# SAML21_Xplained_Pro_EDBG.net
KiCad netlist of a schematic drawn in Altium Designer
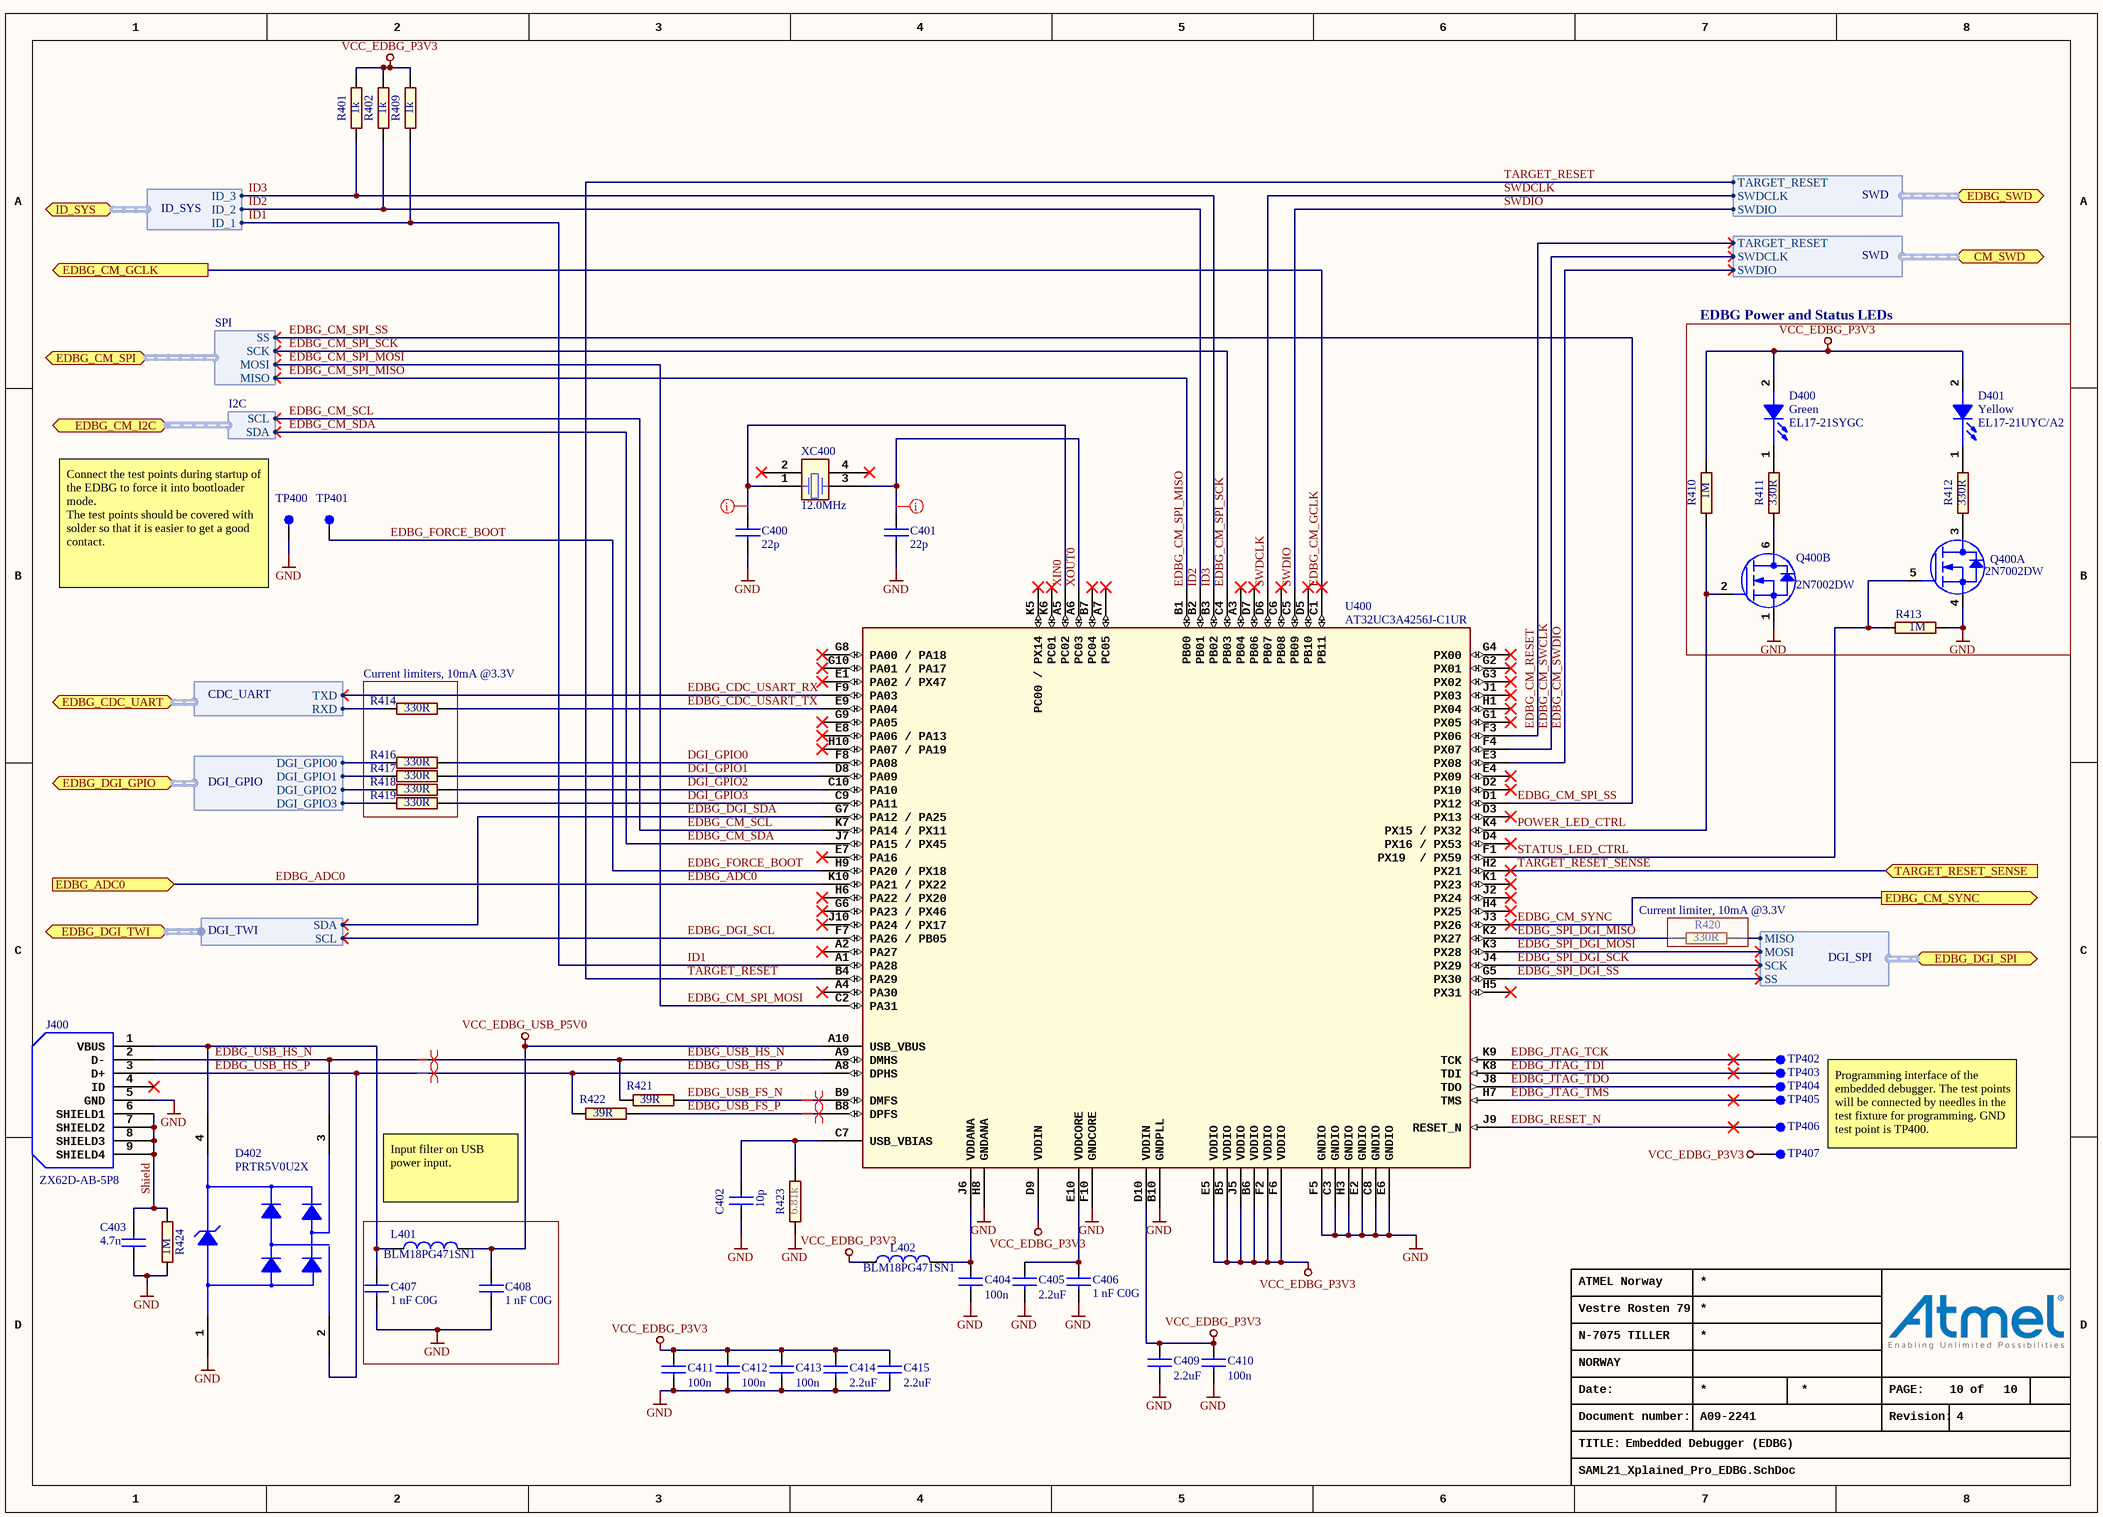
[diagram p0: SAML21_Xplained_Pro_EDBG.SchDoc]

(export (version "E")
  (design (tool "Eeschema 10.0.6"))
  (components
    (comp (ref "C400")
      (value "22p")
      (footprint "AP1-00053")
      (description "Ceramic capacitor, SMD 0402, NP0, 50V, +/-5%")
      (fields (field (name "TOLERANCE") "50V, +/-5%"))
      (libsource (lib "AltiumDbLib") (part "CAP-NONPOL"))
    )
    (comp (ref "C401")
      (value "22p")
      (footprint "AP1-00053")
      (description "Ceramic capacitor, SMD 0402, NP0, 50V, +/-5%")
      (fields (field (name "TOLERANCE") "50V, +/-5%"))
      (libsource (lib "AltiumDbLib") (part "CAP-NONPOL"))
    )
    (comp (ref "C402")
      (value "10p")
      (footprint "AP1-00053")
      (description "Ceramic capacitor, SMD 0402, NP0, 50V, +/-5%")
      (fields (field (name "TOLERANCE") "50V, +/-5%"))
      (libsource (lib "AltiumDbLib") (part "CAP-NONPOL"))
    )
    (comp (ref "C403")
      (value "4.7n")
      (footprint "AP1-00053")
      (description "Ceramic capacitor, SMD 0402, X7R, 25V, +/-10%")
      (fields (field (name "TOLERANCE") "25V, +/-10%") (field (name "Comment") "CAP-NONPOL"))
      (libsource (lib "AltiumDbLib") (part "CAP-NONPOL"))
    )
    (comp (ref "C404")
      (value "100n")
      (footprint "AP1-00053")
      (description "Ceramic capacitor, SMD 0402, X7R, 16V, +/-10%")
      (fields (field (name "TOLERANCE") "16V, +/-10%") (field (name "MANUFACTURER") "Kemet"))
      (libsource (lib "AltiumDbLib") (part "CAP-NONPOL"))
    )
    (comp (ref "C405")
      (value "2.2uF")
      (footprint "AP1-00053")
      (description "Ceramic capacitor, SMD 0402, X5R, 6.3V, +/-20%")
      (fields (field (name "TOLERANCE") "±20%") (field (name "MANUFACTURER") "Kemet"))
      (libsource (lib "AltiumDbLib") (part "CAP-NONPOL"))
    )
    (comp (ref "C406")
      (value "1 nF C0G")
      (footprint "AP1-00053")
      (description "Ceramic capacitor, SMD 0402, C0G, 50V, +/-5%")
      (fields (field (name "TOLERANCE") "5%") (field (name "MANUFACTURER") "Murata"))
      (libsource (lib "AltiumDbLib") (part "CAP-NONPOL"))
    )
    (comp (ref "C407")
      (value "1 nF C0G")
      (footprint "AP1-00053")
      (description "Ceramic capacitor, SMD 0402, C0G, 50V, +/-5%")
      (fields (field (name "TOLERANCE") "5%") (field (name "MANUFACTURER") "Murata"))
      (libsource (lib "AltiumDbLib") (part "CAP-NONPOL"))
    )
    (comp (ref "C408")
      (value "1 nF C0G")
      (footprint "AP1-00053")
      (description "Ceramic capacitor, SMD 0402, C0G, 50V, +/-5%")
      (fields (field (name "TOLERANCE") "5%") (field (name "MANUFACTURER") "Murata"))
      (libsource (lib "AltiumDbLib") (part "CAP-NONPOL"))
    )
    (comp (ref "C409")
      (value "2.2uF")
      (footprint "AP1-00053")
      (description "Ceramic capacitor, SMD 0402, X5R, 6.3V, +/-20%")
      (fields (field (name "TOLERANCE") "±20%") (field (name "MANUFACTURER") "Kemet"))
      (libsource (lib "AltiumDbLib") (part "CAP-NONPOL"))
    )
    (comp (ref "C410")
      (value "100n")
      (footprint "AP1-00053")
      (description "Ceramic capacitor, SMD 0402, X7R, 16V, +/-10%")
      (fields (field (name "TOLERANCE") "16V, +/-10%") (field (name "MANUFACTURER") "Kemet"))
      (libsource (lib "AltiumDbLib") (part "CAP-NONPOL"))
    )
    (comp (ref "C411")
      (value "100n")
      (footprint "AP1-00053")
      (description "Ceramic capacitor, SMD 0402, X7R, 16V, +/-10%")
      (fields (field (name "TOLERANCE") "16V, +/-10%") (field (name "MANUFACTURER") "Kemet"))
      (libsource (lib "AltiumDbLib") (part "CAP-NONPOL"))
    )
    (comp (ref "C412")
      (value "100n")
      (footprint "AP1-00053")
      (description "Ceramic capacitor, SMD 0402, X7R, 16V, +/-10%")
      (fields (field (name "TOLERANCE") "16V, +/-10%") (field (name "MANUFACTURER") "Kemet"))
      (libsource (lib "AltiumDbLib") (part "CAP-NONPOL"))
    )
    (comp (ref "C413")
      (value "100n")
      (footprint "AP1-00053")
      (description "Ceramic capacitor, SMD 0402, X7R, 16V, +/-10%")
      (fields (field (name "TOLERANCE") "16V, +/-10%") (field (name "MANUFACTURER") "Kemet"))
      (libsource (lib "AltiumDbLib") (part "CAP-NONPOL"))
    )
    (comp (ref "C414")
      (value "2.2uF")
      (footprint "AP1-00053")
      (description "Ceramic capacitor, SMD 0402, X5R, 6.3V, +/-20%")
      (fields (field (name "TOLERANCE") "±20%") (field (name "MANUFACTURER") "Kemet"))
      (libsource (lib "AltiumDbLib") (part "CAP-NONPOL"))
    )
    (comp (ref "C415")
      (value "2.2uF")
      (footprint "AP1-00053")
      (description "Ceramic capacitor, SMD 0402, X5R, 6.3V, +/-20%")
      (fields (field (name "TOLERANCE") "±20%") (field (name "MANUFACTURER") "Kemet"))
      (libsource (lib "AltiumDbLib") (part "CAP-NONPOL"))
    )
    (comp (ref "D400")
      (value "Green")
      (footprint "AP4-00013")
      (description "LED, Green, Wave length=575nm, SMD 0805, ±70°")
      (fields
        (field (name "ALTIUM_VALUE") "EL17-21SYGC")
        (field (name "MANUFACTURER") "Everlight")
        (field (name "MPN") "EL17-21SYGC")
      )
      (libsource (lib "AltiumDbLib") (part "LED_12"))
    )
    (comp (ref "D401")
      (value "Yellow")
      (footprint "AP4-00013")
      (description "LED, Yellow, Wave length=591nm, SMD 0805, ±70°")
      (fields
        (field (name "ALTIUM_VALUE") "EL17-21UYC/A2")
        (field (name "MANUFACTURER") "Everlight")
        (field (name "MPN") "17-21UYC/S530-A3/TR8")
      )
      (libsource (lib "AltiumDbLib") (part "LED_12"))
    )
    (comp (ref "D402")
      (value "PRTR5V0U2X")
      (footprint "AP4-00001")
      (description "Double rail-to-rail USB ESD protection diode")
      (fields (field (name "MANUFACTURER") "Philips"))
      (libsource (lib "AltiumDbLib") (part "PRTR5V0U2X"))
    )
    (comp (ref "J400")
      (value "ZX62D-AB-5P8")
      (footprint "AP8-00852")
      (description "Micro USB AB Connector, Standard SMT + DIP")
      (fields (field (name "Comment") "2,000 pieces per reel"))
      (libsource (lib "AltiumDbLib") (part "USB_AB"))
    )
    (comp (ref "L401")
      (value "BLM18PG471SN1")
      (footprint "AP3-00005")
      (description "SMD RF inductor 0603. Z=470Ohm (@100MHz), Max R(dc)=0.65Ohm, Max current=1A")
      (fields (field (name "TOLERANCE") "±25%") (field (name "MANUFACTURER") "Murata"))
      (libsource (lib "AltiumDbLib") (part "INDUCTOR"))
    )
    (comp (ref "L402")
      (value "BLM18PG471SN1")
      (footprint "AP3-00005")
      (description "SMD RF inductor 0603. Z=470Ohm (@100MHz), Max R(dc)=0.65Ohm, Max current=1A")
      (fields (field (name "TOLERANCE") "±25%") (field (name "MANUFACTURER") "Murata"))
      (libsource (lib "AltiumDbLib") (part "INDUCTOR"))
    )
    (comp (ref "Q400")
      (value "2N7002DW")
      (footprint "AP5-00001")
      (description "Dual N-Channel MOSFET, 60V, 115mA cont,RDS(ON) < 7.5 Ohm @50mA@5V, SOT-363")
      (fields
        (field (name "MANUFACTURER") "Fairchild")
        (field (name "Comment") "Same as 2N7002 but with two MOSFETs in one package")
      )
      (libsource (lib "AltiumDbLib") (part "MOSFET_DUAL_N_S2G2D1S1G1D2"))
    )
    (comp (ref "R401")
      (value "1k")
      (footprint "AP2-00000")
      (description "Thick film resistor, SMD 0402, 1/16W, 1%")
      (fields (field (name "TOLERANCE") "1 %") (field (name "Comment") "R2"))
      (libsource (lib "") (part "R2_4"))
    )
    (comp (ref "R402")
      (value "1k")
      (footprint "AP2-00000")
      (description "Thick film resistor, SMD 0402, 1/16W, 1%")
      (fields (field (name "TOLERANCE") "1 %") (field (name "Comment") "R2"))
      (libsource (lib "") (part "R2_4"))
    )
    (comp (ref "R409")
      (value "1k")
      (footprint "AP2-00000")
      (description "Thick film resistor, SMD 0402, 1/16W, 1%")
      (fields (field (name "TOLERANCE") "1 %") (field (name "Comment") "R2"))
      (libsource (lib "") (part "R2_4"))
    )
    (comp (ref "R410")
      (value "1M")
      (footprint "AP2-00011")
      (description "Thick film resistor, SMD 0402, 1/16W, 1%")
      (fields (field (name "TOLERANCE") "1 %") (field (name "MANUFACTURER") "KOA"))
      (libsource (lib "") (part "R2_4"))
    )
    (comp (ref "R411")
      (value "330R")
      (footprint "AP2-00011")
      (description "Thick film resistor, SMD 0402, 1/16W, 1%")
      (fields (field (name "TOLERANCE") "1 %") (field (name "Comment") "R2"))
      (libsource (lib "") (part "R2_4"))
    )
    (comp (ref "R412")
      (value "330R")
      (footprint "AP2-00011")
      (description "Thick film resistor, SMD 0402, 1/16W, 1%")
      (fields (field (name "TOLERANCE") "1 %") (field (name "Comment") "R2"))
      (libsource (lib "") (part "R2_4"))
    )
    (comp (ref "R413")
      (value "1M")
      (footprint "AP2-00011")
      (description "Thick film resistor, SMD 0402, 1/16W, 1%")
      (fields (field (name "TOLERANCE") "1 %") (field (name "MANUFACTURER") "KOA"))
      (libsource (lib "") (part "R2_1"))
    )
    (comp (ref "R414")
      (value "330R")
      (footprint "AP2-00000")
      (description "Thick film resistor, SMD 0402, 1/16W, 1%")
      (fields (field (name "TOLERANCE") "1 %") (field (name "Comment") "R2"))
      (libsource (lib "AltiumDbLib") (part "R2"))
    )
    (comp (ref "R416")
      (value "330R")
      (footprint "AP2-00000")
      (description "Thick film resistor, SMD 0402, 1/16W, 1%")
      (fields (field (name "TOLERANCE") "1 %") (field (name "Comment") "R2"))
      (libsource (lib "AltiumDbLib") (part "R2"))
    )
    (comp (ref "R417")
      (value "330R")
      (footprint "AP2-00000")
      (description "Thick film resistor, SMD 0402, 1/16W, 1%")
      (fields (field (name "TOLERANCE") "1 %") (field (name "Comment") "R2"))
      (libsource (lib "AltiumDbLib") (part "R2"))
    )
    (comp (ref "R418")
      (value "330R")
      (footprint "AP2-00000")
      (description "Thick film resistor, SMD 0402, 1/16W, 1%")
      (fields (field (name "TOLERANCE") "1 %") (field (name "Comment") "R2"))
      (libsource (lib "AltiumDbLib") (part "R2"))
    )
    (comp (ref "R419")
      (value "330R")
      (footprint "AP2-00000")
      (description "Thick film resistor, SMD 0402, 1/16W, 1%")
      (fields (field (name "TOLERANCE") "1 %") (field (name "Comment") "R2"))
      (libsource (lib "AltiumDbLib") (part "R2"))
    )
    (comp (ref "R420")
      (value "330R")
      (footprint "AP2-00000")
      (description "Thick film resistor, SMD 0402, 1/16W, 1%")
      (fields (field (name "TOLERANCE") "1 %") (field (name "Comment") "R2"))
      (libsource (lib "AltiumDbLib") (part "R2"))
    )
    (comp (ref "R421")
      (value "39R")
      (footprint "AP2-00011")
      (description "Thick film resistor, SMD 0402, 1/16W, 1%")
      (fields (field (name "TOLERANCE") "1 %") (field (name "Comment") "R2"))
      (libsource (lib "") (part "R2_3"))
    )
    (comp (ref "R422")
      (value "39R")
      (footprint "AP2-00011")
      (description "Thick film resistor, SMD 0402, 1/16W, 1%")
      (fields (field (name "TOLERANCE") "1 %") (field (name "Comment") "R2"))
      (libsource (lib "") (part "R2_3"))
    )
    (comp (ref "R423")
      (value "6.81k")
      (footprint "AP2-00011")
      (description "Thick film resistor, SMD 0402, 1/16W, 1%")
      (fields (field (name "TOLERANCE") "1%") (field (name "Comment") "R2"))
      (libsource (lib "") (part "R2_4"))
    )
    (comp (ref "R424")
      (value "1M")
      (footprint "AP2-00011")
      (description "Thick film resistor, SMD 0402, 1/16W, 1%")
      (fields (field (name "TOLERANCE") "1 %") (field (name "MANUFACTURER") "KOA"))
      (libsource (lib "") (part "R2_2"))
    )
    (comp (ref "TP400")
      (value "TESTPAD")
      (footprint "AP8-00010")
      (description "Single SMD testpad")
      (libsource (lib "AltiumDbLib") (part "TESTPOINT"))
    )
    (comp (ref "TP401")
      (value "TESTPAD")
      (footprint "AP8-00010")
      (description "Single SMD testpad")
      (libsource (lib "AltiumDbLib") (part "TESTPOINT"))
    )
    (comp (ref "TP402")
      (value "TESTPAD")
      (footprint "AP8-00010")
      (description "Single SMD testpad")
      (libsource (lib "AltiumDbLib") (part "TESTPOINT"))
    )
    (comp (ref "TP403")
      (value "TESTPAD")
      (footprint "AP8-00010")
      (description "Single SMD testpad")
      (libsource (lib "AltiumDbLib") (part "TESTPOINT"))
    )
    (comp (ref "TP404")
      (value "TESTPAD")
      (footprint "AP8-00010")
      (description "Single SMD testpad")
      (libsource (lib "AltiumDbLib") (part "TESTPOINT"))
    )
    (comp (ref "TP405")
      (value "TESTPAD")
      (footprint "AP8-00010")
      (description "Single SMD testpad")
      (libsource (lib "AltiumDbLib") (part "TESTPOINT"))
    )
    (comp (ref "TP406")
      (value "TESTPAD")
      (footprint "AP8-00010")
      (description "Single SMD testpad")
      (libsource (lib "AltiumDbLib") (part "TESTPOINT"))
    )
    (comp (ref "TP407")
      (value "TESTPAD")
      (footprint "AP8-00010")
      (description "Single SMD testpad")
      (libsource (lib "AltiumDbLib") (part "TESTPOINT"))
    )
    (comp (ref "U400")
      (value "AT32UC3A4256J-C1UR")
      (footprint "AP6-00206")
      (description "AVR 32-bit RISC MCU")
      (fields (field (name "MANUFACTURER") "ATMEL") (field (name "Comment") "100 ball VFBGA"))
      (libsource (lib "AltiumDbLib") (part "AT32UC3A4_VFBGA"))
    )
    (comp (ref "XC400")
      (value "12.0MHz")
      (footprint "AP7-00039")
      (description "Fox FQ5032B 12.0MHz SMD crystal 738B-12")
      (fields (field (name "TOLERANCE") "30PPM") (field (name "MANUFACTURER") "Fox  Electronics"))
      (libsource (lib "AltiumDbLib") (part "CRYSTAL1324"))
    )
  )
  (nets
    (net (code "9") (name "/DGI_GPIO0") (class "Default")
      (node (ref "R416") (pin "2") (pinfunction "2_2") (pintype "passive"))
      (node (ref "U400") (pin "F8") (pinfunction "PA08_F8") (pintype "bidirectional"))
    )
    (net (code "10") (name "/DGI_GPIO1") (class "Default")
      (node (ref "R417") (pin "2") (pinfunction "2_2") (pintype "passive"))
      (node (ref "U400") (pin "D8") (pinfunction "PA09_D8") (pintype "bidirectional"))
    )
    (net (code "11") (name "/DGI_GPIO2") (class "Default")
      (node (ref "R418") (pin "2") (pinfunction "2_2") (pintype "passive"))
      (node (ref "U400") (pin "C10") (pinfunction "PA10_C10") (pintype "bidirectional"))
    )
    (net (code "12") (name "/DGI_GPIO3") (class "Default")
      (node (ref "R419") (pin "2") (pinfunction "2_2") (pintype "passive"))
      (node (ref "U400") (pin "C9") (pinfunction "PA11_C9") (pintype "bidirectional"))
    )
    (net (code "13") (name "/EDBG_ADC0") (class "Default")
      (node (ref "U400") (pin "K10") (pinfunction "PA21_/_PX22_K10") (pintype "bidirectional"))
    )
    (net (code "14") (name "/EDBG_CDC_USART_RX") (class "Default")
      (node (ref "U400") (pin "F9") (pinfunction "PA03_F9") (pintype "bidirectional+no_connect"))
    )
    (net (code "15") (name "/EDBG_CDC_USART_TX") (class "Default")
      (node (ref "R414") (pin "2") (pinfunction "2_2") (pintype "passive"))
      (node (ref "U400") (pin "E9") (pinfunction "PA04_E9") (pintype "bidirectional"))
    )
    (net (code "16") (name "/EDBG_CM_GCLK") (class "Default")
      (node (ref "U400") (pin "C1") (pinfunction "PB11_C1") (pintype "bidirectional+no_connect"))
    )
    (net (code "17") (name "/EDBG_CM_RESET") (class "Default")
      (node (ref "U400") (pin "F3") (pinfunction "PX06_F3") (pintype "bidirectional+no_connect"))
    )
    (net (code "18") (name "/EDBG_CM_SCL") (class "Default")
      (node (ref "U400") (pin "K7") (pinfunction "PA14_/_PX11_K7") (pintype "bidirectional+no_connect"))
    )
    (net (code "19") (name "/EDBG_CM_SDA") (class "Default")
      (node (ref "U400") (pin "J7") (pinfunction "PA15_/_PX45_J7") (pintype "bidirectional+no_connect"))
    )
    (net (code "20") (name "/EDBG_CM_SPI_MISO") (class "Default")
      (node (ref "U400") (pin "B1") (pinfunction "PB00_B1") (pintype "bidirectional+no_connect"))
    )
    (net (code "21") (name "/EDBG_CM_SPI_MOSI") (class "Default")
      (node (ref "U400") (pin "C2") (pinfunction "PA31_C2") (pintype "bidirectional+no_connect"))
    )
    (net (code "22") (name "/EDBG_CM_SPI_SCK") (class "Default")
      (node (ref "U400") (pin "C4") (pinfunction "PB03_C4") (pintype "bidirectional+no_connect"))
    )
    (net (code "23") (name "/EDBG_CM_SPI_SS") (class "Default")
      (node (ref "U400") (pin "D1") (pinfunction "PX12_D1") (pintype "bidirectional+no_connect"))
    )
    (net (code "24") (name "/EDBG_CM_SWCLK") (class "Default")
      (node (ref "U400") (pin "F4") (pinfunction "PX07_F4") (pintype "bidirectional+no_connect"))
    )
    (net (code "25") (name "/EDBG_CM_SWDIO") (class "Default")
      (node (ref "U400") (pin "E3") (pinfunction "PX08_E3") (pintype "bidirectional+no_connect"))
    )
    (net (code "26") (name "/EDBG_CM_SYNC") (class "Default")
      (node (ref "U400") (pin "J3") (pinfunction "PX26_J3") (pintype "bidirectional+no_connect"))
    )
    (net (code "27") (name "/EDBG_DGI_SCL") (class "Default")
      (node (ref "U400") (pin "F7") (pinfunction "PA26_/_PB05_F7") (pintype "bidirectional+no_connect"))
    )
    (net (code "28") (name "/EDBG_DGI_SDA") (class "Default")
      (node (ref "U400") (pin "G7") (pinfunction "PA12_/_PA25_G7") (pintype "bidirectional+no_connect"))
    )
    (net (code "29") (name "/EDBG_FORCE_BOOT") (class "Default")
      (node (ref "TP401") (pin "1") (pinfunction "1_1") (pintype "passive"))
      (node (ref "U400") (pin "H9") (pinfunction "PA20_/_PX18_H9") (pintype "bidirectional"))
    )
    (net (code "30") (name "/EDBG_JTAG_TCK") (class "Default")
      (node (ref "TP402") (pin "1") (pinfunction "1_1") (pintype "passive"))
      (node (ref "U400") (pin "K9") (pinfunction "TCK_K9") (pintype "input"))
    )
    (net (code "31") (name "/EDBG_JTAG_TDI") (class "Default")
      (node (ref "TP403") (pin "1") (pinfunction "1_1") (pintype "passive"))
      (node (ref "U400") (pin "K8") (pinfunction "TDI_K8") (pintype "input"))
    )
    (net (code "32") (name "/EDBG_JTAG_TDO") (class "Default")
      (node (ref "TP404") (pin "1") (pinfunction "1_1") (pintype "passive"))
      (node (ref "U400") (pin "J8") (pinfunction "TDO_J8") (pintype "output"))
    )
    (net (code "33") (name "/EDBG_JTAG_TMS") (class "Default")
      (node (ref "TP405") (pin "1") (pinfunction "1_1") (pintype "passive"))
      (node (ref "U400") (pin "H7") (pinfunction "TMS_H7") (pintype "input"))
    )
    (net (code "34") (name "/EDBG_RESET_N") (class "Default")
      (node (ref "TP406") (pin "1") (pinfunction "1_1") (pintype "passive"))
      (node (ref "U400") (pin "J9") (pinfunction "RESET_N_J9") (pintype "input"))
    )
    (net (code "35") (name "/EDBG_SPI_DGI_MISO") (class "Default")
      (node (ref "R420") (pin "1") (pinfunction "1_1") (pintype "passive"))
      (node (ref "U400") (pin "K2") (pinfunction "PX27_K2") (pintype "bidirectional"))
    )
    (net (code "36") (name "/EDBG_SPI_DGI_MOSI") (class "Default")
      (node (ref "U400") (pin "K3") (pinfunction "PX28_K3") (pintype "bidirectional+no_connect"))
    )
    (net (code "37") (name "/EDBG_SPI_DGI_SCK") (class "Default")
      (node (ref "U400") (pin "J4") (pinfunction "PX29_J4") (pintype "bidirectional+no_connect"))
    )
    (net (code "38") (name "/EDBG_SPI_DGI_SS") (class "Default")
      (node (ref "U400") (pin "G5") (pinfunction "PX30_G5") (pintype "bidirectional+no_connect"))
    )
    (net (code "39") (name "/EDBG_USB_FS_N") (class "Default")
      (node (ref "R421") (pin "2") (pinfunction "2_2") (pintype "passive"))
      (node (ref "U400") (pin "B9") (pinfunction "DMFS_B9") (pintype "bidirectional"))
    )
    (net (code "40") (name "/EDBG_USB_FS_P") (class "Default")
      (node (ref "R422") (pin "2") (pinfunction "2_2") (pintype "passive"))
      (node (ref "U400") (pin "B8") (pinfunction "DPFS_B8") (pintype "bidirectional"))
    )
    (net (code "41") (name "/EDBG_USB_HS_N") (class "Default")
      (node (ref "D402") (pin "3") (pinfunction "I/O_2_3") (pintype "passive"))
      (node (ref "J400") (pin "2") (pinfunction "D-_2") (pintype "passive"))
      (node (ref "R421") (pin "1") (pinfunction "1_1") (pintype "passive"))
      (node (ref "U400") (pin "A9") (pinfunction "DMHS_A9") (pintype "bidirectional"))
    )
    (net (code "42") (name "/EDBG_USB_HS_P") (class "Default")
      (node (ref "D402") (pin "2") (pinfunction "I/O_1_2") (pintype "passive"))
      (node (ref "J400") (pin "3") (pinfunction "D+_3") (pintype "passive"))
      (node (ref "R422") (pin "1") (pinfunction "1_1") (pintype "passive"))
      (node (ref "U400") (pin "A8") (pinfunction "DPHS_A8") (pintype "bidirectional"))
    )
    (net (code "43") (name "/ID1") (class "Default")
      (node (ref "R409") (pin "1") (pinfunction "1_1") (pintype "passive"))
      (node (ref "U400") (pin "A1") (pinfunction "PA28_A1") (pintype "bidirectional"))
    )
    (net (code "44") (name "/ID2") (class "Default")
      (node (ref "R402") (pin "1") (pinfunction "1_1") (pintype "passive"))
      (node (ref "U400") (pin "B2") (pinfunction "PB01_B2") (pintype "bidirectional"))
    )
    (net (code "45") (name "/ID3") (class "Default")
      (node (ref "R401") (pin "1") (pinfunction "1_1") (pintype "passive"))
      (node (ref "U400") (pin "B3") (pinfunction "PB02_B3") (pintype "bidirectional"))
    )
    (net (code "46") (name "/POWER_LED_CTRL") (class "Default")
      (node (ref "Q400") (pin "2") (pinfunction "G2_2") (pintype "passive"))
      (node (ref "R410") (pin "1") (pinfunction "1_1") (pintype "passive"))
      (node (ref "U400") (pin "K4") (pinfunction "PX15_/_PX32_K4") (pintype "bidirectional"))
    )
    (net (code "47") (name "/RXD") (class "Default")
      (node (ref "R414") (pin "1") (pinfunction "1_1") (pintype "passive"))
    )
    (net (code "48") (name "/STATUS_LED_CTRL") (class "Default")
      (node (ref "Q400") (pin "5") (pinfunction "G1_5") (pintype "passive"))
      (node (ref "R413") (pin "2") (pinfunction "2_2") (pintype "passive"))
      (node (ref "U400") (pin "F1") (pinfunction "PX19__/_PX59_F1") (pintype "bidirectional"))
    )
    (net (code "49") (name "/SWDCLK") (class "Default")
      (node (ref "U400") (pin "D6") (pinfunction "PB07_D6") (pintype "bidirectional"))
    )
    (net (code "50") (name "/SWDIO") (class "Default")
      (node (ref "U400") (pin "C5") (pinfunction "PB09_C5") (pintype "bidirectional"))
    )
    (net (code "51") (name "/Shield") (class "Default")
      (node (ref "C403") (pin "2") (pinfunction "2_2") (pintype "passive"))
      (node (ref "J400") (pin "6") (pinfunction "SHIELD1_6") (pintype "passive"))
      (node (ref "J400") (pin "7") (pinfunction "SHIELD2_7") (pintype "passive"))
      (node (ref "J400") (pin "8") (pinfunction "SHIELD3_8") (pintype "passive"))
      (node (ref "J400") (pin "9") (pinfunction "SHIELD4_9") (pintype "passive"))
      (node (ref "R424") (pin "2") (pinfunction "2_2") (pintype "passive"))
    )
    (net (code "52") (name "/TARGET_RESET") (class "Default")
      (node (ref "U400") (pin "B4") (pinfunction "PA29_B4") (pintype "bidirectional"))
    )
    (net (code "53") (name "/TARGET_RESET_SENSE") (class "Default")
      (node (ref "U400") (pin "H2") (pinfunction "PX21_H2") (pintype "bidirectional+no_connect"))
    )
    (net (code "54") (name "/XIN0") (class "Default")
      (node (ref "C400") (pin "1") (pinfunction "1_1") (pintype "passive"))
      (node (ref "U400") (pin "A5") (pinfunction "PC02_A5") (pintype "bidirectional"))
      (node (ref "XC400") (pin "1") (pinfunction "1_1") (pintype "passive"))
    )
    (net (code "55") (name "/XOUT0") (class "Default")
      (node (ref "C401") (pin "1") (pinfunction "1_1") (pintype "passive"))
      (node (ref "U400") (pin "A6") (pinfunction "PC03_A6") (pintype "bidirectional"))
      (node (ref "XC400") (pin "3") (pinfunction "3_3") (pintype "passive"))
    )
    (net (code "64") (name "GND") (class "Default")
      (node (ref "C400") (pin "2") (pinfunction "2_2") (pintype "passive"))
      (node (ref "C401") (pin "2") (pinfunction "2_2") (pintype "passive"))
      (node (ref "C402") (pin "2") (pinfunction "2_2") (pintype "passive"))
      (node (ref "C403") (pin "1") (pinfunction "1_1") (pintype "passive"))
      (node (ref "C404") (pin "2") (pinfunction "2_2") (pintype "passive"))
      (node (ref "C405") (pin "2") (pinfunction "2_2") (pintype "passive"))
      (node (ref "C406") (pin "2") (pinfunction "2_2") (pintype "passive"))
      (node (ref "C407") (pin "2") (pinfunction "2_2") (pintype "passive"))
      (node (ref "C408") (pin "2") (pinfunction "2_2") (pintype "passive"))
      (node (ref "C409") (pin "2") (pinfunction "2_2") (pintype "passive"))
      (node (ref "C410") (pin "2") (pinfunction "2_2") (pintype "passive"))
      (node (ref "C411") (pin "2") (pinfunction "2_2") (pintype "passive"))
      (node (ref "C412") (pin "2") (pinfunction "2_2") (pintype "passive"))
      (node (ref "C413") (pin "2") (pinfunction "2_2") (pintype "passive"))
      (node (ref "C414") (pin "2") (pinfunction "2_2") (pintype "passive"))
      (node (ref "C415") (pin "2") (pinfunction "2_2") (pintype "passive"))
      (node (ref "D402") (pin "1") (pinfunction "GND_1") (pintype "passive"))
      (node (ref "J400") (pin "5") (pinfunction "GND_5") (pintype "passive"))
      (node (ref "Q400") (pin "1") (pinfunction "S2_1") (pintype "passive"))
      (node (ref "Q400") (pin "4") (pinfunction "S1_4") (pintype "passive"))
      (node (ref "R413") (pin "1") (pinfunction "1_1") (pintype "passive"))
      (node (ref "R423") (pin "1") (pinfunction "1_1") (pintype "passive"))
      (node (ref "R424") (pin "1") (pinfunction "1_1") (pintype "passive"))
      (node (ref "TP400") (pin "1") (pinfunction "1_1") (pintype "passive"))
      (node (ref "U400") (pin "B10") (pinfunction "GNDPLL_B10") (pintype "power_in"))
      (node (ref "U400") (pin "C3") (pinfunction "GNDIO_C3") (pintype "power_in"))
      (node (ref "U400") (pin "C8") (pinfunction "GNDIO_C8") (pintype "power_in"))
      (node (ref "U400") (pin "E2") (pinfunction "GNDIO_E2") (pintype "power_in"))
      (node (ref "U400") (pin "E6") (pinfunction "GNDIO_E6") (pintype "power_in"))
      (node (ref "U400") (pin "F10") (pinfunction "GNDCORE_F10") (pintype "power_in"))
      (node (ref "U400") (pin "F5") (pinfunction "GNDIO_F5") (pintype "power_in"))
      (node (ref "U400") (pin "H3") (pinfunction "GNDIO_H3") (pintype "power_in"))
      (node (ref "U400") (pin "H8") (pinfunction "GNDANA_H8") (pintype "power_in"))
    )
    (net (code "65") (name "Net-(D400-CATHODE)") (class "Default")
      (node (ref "D400") (pin "1") (pinfunction "CATHODE_1") (pintype "passive"))
      (node (ref "R411") (pin "2") (pinfunction "2_2") (pintype "passive"))
    )
    (net (code "66") (name "Net-(D401-CATHODE)") (class "Default")
      (node (ref "D401") (pin "1") (pinfunction "CATHODE_1") (pintype "passive"))
      (node (ref "R412") (pin "2") (pinfunction "2_2") (pintype "passive"))
    )
    (net (code "67") (name "Net-(D402-VCC)") (class "Default")
      (node (ref "C407") (pin "1") (pinfunction "1_1") (pintype "passive"))
      (node (ref "D402") (pin "4") (pinfunction "VCC_4") (pintype "passive"))
      (node (ref "J400") (pin "1") (pinfunction "VBUS_1") (pintype "passive"))
      (node (ref "L401") (pin "1") (pinfunction "1_1") (pintype "passive"))
    )
    (net (code "68") (name "Net-(Q400A-D1)") (class "Default")
      (node (ref "Q400") (pin "3") (pinfunction "D1_3") (pintype "passive"))
      (node (ref "R412") (pin "1") (pinfunction "1_1") (pintype "passive"))
    )
    (net (code "69") (name "Net-(Q400B-D2)") (class "Default")
      (node (ref "Q400") (pin "6") (pinfunction "D2_6") (pintype "passive"))
      (node (ref "R411") (pin "1") (pinfunction "1_1") (pintype "passive"))
    )
    (net (code "70") (name "Net-(U400-USB_VBIAS)") (class "Default")
      (node (ref "C402") (pin "1") (pinfunction "1_1") (pintype "passive"))
      (node (ref "R423") (pin "2") (pinfunction "2_2") (pintype "passive"))
      (node (ref "U400") (pin "C7") (pinfunction "USB_VBIAS_C7") (pintype "power_in"))
    )
    (net (code "71") (name "Net-(U400-VDDANA)") (class "Default")
      (node (ref "C404") (pin "1") (pinfunction "1_1") (pintype "passive"))
      (node (ref "L402") (pin "2") (pinfunction "2_2") (pintype "passive"))
      (node (ref "U400") (pin "J6") (pinfunction "VDDANA_J6") (pintype "power_in"))
    )
    (net (code "72") (name "Net-(U400-VDDCORE)") (class "Default")
      (node (ref "C405") (pin "1") (pinfunction "1_1") (pintype "passive"))
      (node (ref "C406") (pin "1") (pinfunction "1_1") (pintype "passive"))
      (node (ref "U400") (pin "E10") (pinfunction "VDDCORE_E10") (pintype "power_in"))
    )
    (net (code "73") (name "VCC_EDBG_P3V3") (class "Default")
      (node (ref "C409") (pin "1") (pinfunction "1_1") (pintype "passive"))
      (node (ref "C410") (pin "1") (pinfunction "1_1") (pintype "passive"))
      (node (ref "C411") (pin "1") (pinfunction "1_1") (pintype "passive"))
      (node (ref "C412") (pin "1") (pinfunction "1_1") (pintype "passive"))
      (node (ref "C413") (pin "1") (pinfunction "1_1") (pintype "passive"))
      (node (ref "C414") (pin "1") (pinfunction "1_1") (pintype "passive"))
      (node (ref "C415") (pin "1") (pinfunction "1_1") (pintype "passive"))
      (node (ref "D400") (pin "2") (pinfunction "ANODE_2") (pintype "passive"))
      (node (ref "D401") (pin "2") (pinfunction "ANODE_2") (pintype "passive"))
      (node (ref "L402") (pin "1") (pinfunction "1_1") (pintype "passive"))
      (node (ref "R401") (pin "2") (pinfunction "2_2") (pintype "passive"))
      (node (ref "R402") (pin "2") (pinfunction "2_2") (pintype "passive"))
      (node (ref "R409") (pin "2") (pinfunction "2_2") (pintype "passive"))
      (node (ref "R410") (pin "2") (pinfunction "2_2") (pintype "passive"))
      (node (ref "TP407") (pin "1") (pinfunction "1_1") (pintype "passive"))
      (node (ref "U400") (pin "B5") (pinfunction "VDDIO_B5") (pintype "power_in"))
      (node (ref "U400") (pin "B6") (pinfunction "VDDIO_B6") (pintype "power_in"))
      (node (ref "U400") (pin "D10") (pinfunction "VDDIN_D10") (pintype "power_in"))
      (node (ref "U400") (pin "D9") (pinfunction "VDDIN_D9") (pintype "power_in"))
      (node (ref "U400") (pin "E5") (pinfunction "VDDIO_E5") (pintype "power_in"))
      (node (ref "U400") (pin "F2") (pinfunction "VDDIO_F2") (pintype "power_in"))
      (node (ref "U400") (pin "F6") (pinfunction "VDDIO_F6") (pintype "power_in"))
      (node (ref "U400") (pin "J5") (pinfunction "VDDIO_J5") (pintype "power_in"))
    )
    (net (code "74") (name "VCC_EDBG_USB_P5V0") (class "Default")
      (node (ref "C408") (pin "1") (pinfunction "1_1") (pintype "passive"))
      (node (ref "L401") (pin "2") (pinfunction "2_2") (pintype "passive"))
      (node (ref "U400") (pin "A10") (pinfunction "USB_VBUS_A10") (pintype "power_in"))
    )
    (net (code "75") (name "unconnected-(J400-ID-Pad4)") (class "Default")
      (node (ref "J400") (pin "4") (pinfunction "ID_4") (pintype "passive+no_connect"))
    )
    (net (code "76") (name "unconnected-(R416-Pad1)") (class "Default")
      (node (ref "R416") (pin "1") (pinfunction "1_1") (pintype "passive"))
    )
    (net (code "77") (name "unconnected-(R417-Pad1)") (class "Default")
      (node (ref "R417") (pin "1") (pinfunction "1_1") (pintype "passive"))
    )
    (net (code "78") (name "unconnected-(R418-Pad1)") (class "Default")
      (node (ref "R418") (pin "1") (pinfunction "1_1") (pintype "passive"))
    )
    (net (code "79") (name "unconnected-(R419-Pad1)") (class "Default")
      (node (ref "R419") (pin "1") (pinfunction "1_1") (pintype "passive"))
    )
    (net (code "80") (name "unconnected-(R420-Pad2)") (class "Default")
      (node (ref "R420") (pin "2") (pinfunction "2_2") (pintype "passive"))
    )
    (net (code "81") (name "unconnected-(U400-PA00_{slash}_PA18-PadG8)") (class "Default")
      (node (ref "U400") (pin "G8") (pinfunction "PA00_/_PA18_G8") (pintype "bidirectional+no_connect"))
    )
    (net (code "82") (name "unconnected-(U400-PA01_{slash}_PA17-PadG10)") (class "Default")
      (node (ref "U400") (pin "G10") (pinfunction "PA01_/_PA17_G10") (pintype "bidirectional+no_connect"))
    )
    (net (code "83") (name "unconnected-(U400-PA02_{slash}_PX47-PadE1)") (class "Default")
      (node (ref "U400") (pin "E1") (pinfunction "PA02_/_PX47_E1") (pintype "bidirectional+no_connect"))
    )
    (net (code "84") (name "unconnected-(U400-PA05-PadG9)") (class "Default")
      (node (ref "U400") (pin "G9") (pinfunction "PA05_G9") (pintype "bidirectional+no_connect"))
    )
    (net (code "85") (name "unconnected-(U400-PA06_{slash}_PA13-PadE8)") (class "Default")
      (node (ref "U400") (pin "E8") (pinfunction "PA06_/_PA13_E8") (pintype "bidirectional+no_connect"))
    )
    (net (code "86") (name "unconnected-(U400-PA07_{slash}_PA19-PadH10)") (class "Default")
      (node (ref "U400") (pin "H10") (pinfunction "PA07_/_PA19_H10") (pintype "bidirectional+no_connect"))
    )
    (net (code "87") (name "unconnected-(U400-PA16-PadE7)") (class "Default")
      (node (ref "U400") (pin "E7") (pinfunction "PA16_E7") (pintype "bidirectional+no_connect"))
    )
    (net (code "88") (name "unconnected-(U400-PA22_{slash}_PX20-PadH6)") (class "Default")
      (node (ref "U400") (pin "H6") (pinfunction "PA22_/_PX20_H6") (pintype "bidirectional+no_connect"))
    )
    (net (code "89") (name "unconnected-(U400-PA23_{slash}_PX46-PadG6)") (class "Default")
      (node (ref "U400") (pin "G6") (pinfunction "PA23_/_PX46_G6") (pintype "bidirectional+no_connect"))
    )
    (net (code "90") (name "unconnected-(U400-PA24_{slash}_PX17-PadJ10)") (class "Default")
      (node (ref "U400") (pin "J10") (pinfunction "PA24_/_PX17_J10") (pintype "bidirectional+no_connect"))
    )
    (net (code "91") (name "unconnected-(U400-PA27-PadA2)") (class "Default")
      (node (ref "U400") (pin "A2") (pinfunction "PA27_A2") (pintype "bidirectional+no_connect"))
    )
    (net (code "92") (name "unconnected-(U400-PA30-PadA4)") (class "Default")
      (node (ref "U400") (pin "A4") (pinfunction "PA30_A4") (pintype "bidirectional+no_connect"))
    )
    (net (code "93") (name "unconnected-(U400-PB04-PadA3)") (class "Default")
      (node (ref "U400") (pin "A3") (pinfunction "PB04_A3") (pintype "bidirectional+no_connect"))
    )
    (net (code "94") (name "unconnected-(U400-PB06-PadD7)") (class "Default")
      (node (ref "U400") (pin "D7") (pinfunction "PB06_D7") (pintype "bidirectional+no_connect"))
    )
    (net (code "95") (name "unconnected-(U400-PB08-PadC6)") (class "Default")
      (node (ref "U400") (pin "C6") (pinfunction "PB08_C6") (pintype "bidirectional+no_connect"))
    )
    (net (code "96") (name "unconnected-(U400-PB10-PadD5)") (class "Default")
      (node (ref "U400") (pin "D5") (pinfunction "PB10_D5") (pintype "bidirectional+no_connect"))
    )
    (net (code "97") (name "unconnected-(U400-PC00_{slash}_PX14-PadK5)") (class "Default")
      (node (ref "U400") (pin "K5") (pinfunction "PC00_/_PX14_K5") (pintype "bidirectional+no_connect"))
    )
    (net (code "98") (name "unconnected-(U400-PC01-PadK6)") (class "Default")
      (node (ref "U400") (pin "K6") (pinfunction "PC01_K6") (pintype "bidirectional+no_connect"))
    )
    (net (code "99") (name "unconnected-(U400-PC04-PadB7)") (class "Default")
      (node (ref "U400") (pin "B7") (pinfunction "PC04_B7") (pintype "bidirectional+no_connect"))
    )
    (net (code "100") (name "unconnected-(U400-PC05-PadA7)") (class "Default")
      (node (ref "U400") (pin "A7") (pinfunction "PC05_A7") (pintype "bidirectional+no_connect"))
    )
    (net (code "101") (name "unconnected-(U400-PX00-PadG4)") (class "Default")
      (node (ref "U400") (pin "G4") (pinfunction "PX00_G4") (pintype "bidirectional+no_connect"))
    )
    (net (code "102") (name "unconnected-(U400-PX01-PadG2)") (class "Default")
      (node (ref "U400") (pin "G2") (pinfunction "PX01_G2") (pintype "bidirectional+no_connect"))
    )
    (net (code "103") (name "unconnected-(U400-PX02-PadG3)") (class "Default")
      (node (ref "U400") (pin "G3") (pinfunction "PX02_G3") (pintype "bidirectional+no_connect"))
    )
    (net (code "104") (name "unconnected-(U400-PX03-PadJ1)") (class "Default")
      (node (ref "U400") (pin "J1") (pinfunction "PX03_J1") (pintype "bidirectional+no_connect"))
    )
    (net (code "105") (name "unconnected-(U400-PX04-PadH1)") (class "Default")
      (node (ref "U400") (pin "H1") (pinfunction "PX04_H1") (pintype "bidirectional+no_connect"))
    )
    (net (code "106") (name "unconnected-(U400-PX05-PadG1)") (class "Default")
      (node (ref "U400") (pin "G1") (pinfunction "PX05_G1") (pintype "bidirectional+no_connect"))
    )
    (net (code "107") (name "unconnected-(U400-PX09-PadE4)") (class "Default")
      (node (ref "U400") (pin "E4") (pinfunction "PX09_E4") (pintype "bidirectional+no_connect"))
    )
    (net (code "108") (name "unconnected-(U400-PX10-PadD2)") (class "Default")
      (node (ref "U400") (pin "D2") (pinfunction "PX10_D2") (pintype "bidirectional+no_connect"))
    )
    (net (code "109") (name "unconnected-(U400-PX13-PadD3)") (class "Default")
      (node (ref "U400") (pin "D3") (pinfunction "PX13_D3") (pintype "bidirectional+no_connect"))
    )
    (net (code "110") (name "unconnected-(U400-PX16_{slash}_PX53-PadD4)") (class "Default")
      (node (ref "U400") (pin "D4") (pinfunction "PX16_/_PX53_D4") (pintype "bidirectional+no_connect"))
    )
    (net (code "111") (name "unconnected-(U400-PX23-PadK1)") (class "Default")
      (node (ref "U400") (pin "K1") (pinfunction "PX23_K1") (pintype "bidirectional+no_connect"))
    )
    (net (code "112") (name "unconnected-(U400-PX24-PadJ2)") (class "Default")
      (node (ref "U400") (pin "J2") (pinfunction "PX24_J2") (pintype "bidirectional+no_connect"))
    )
    (net (code "113") (name "unconnected-(U400-PX25-PadH4)") (class "Default")
      (node (ref "U400") (pin "H4") (pinfunction "PX25_H4") (pintype "bidirectional+no_connect"))
    )
    (net (code "114") (name "unconnected-(U400-PX31-PadH5)") (class "Default")
      (node (ref "U400") (pin "H5") (pinfunction "PX31_H5") (pintype "bidirectional+no_connect"))
    )
    (net (code "115") (name "unconnected-(XC400-Pad2)") (class "Default")
      (node (ref "XC400") (pin "2") (pinfunction "2_2") (pintype "passive+no_connect"))
    )
    (net (code "116") (name "unconnected-(XC400-Pad4)") (class "Default")
      (node (ref "XC400") (pin "4") (pinfunction "4_4") (pintype "passive+no_connect"))
    )
  )
)
